# BMS_CellNode.net
KiCad netlist of a schematic drawn in Altium Designer
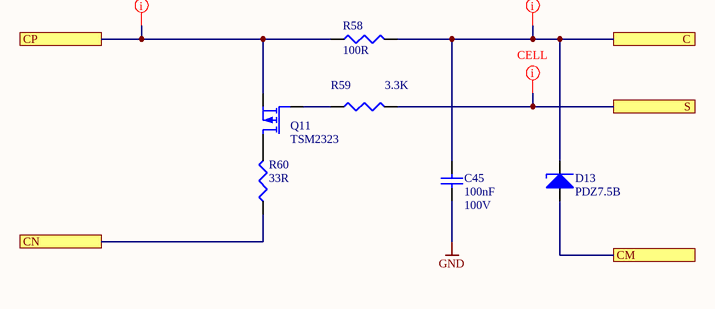
[diagram p0: BMS_CellNode.SchDoc]

(export (version "E")
  (design (tool "Eeschema 10.0.6"))
  (components
    (comp (ref "C45")
      (value "100nF")
      (footprint "VESC_BMS:C-0805")
      (description "Capacitor, 100nF, 100V, X7R")
      (fields (field (name "VOLTAGE RATING") "100V"))
      (libsource (lib "AR_Capacitors_Ceramic") (part "100nF/0805/CER/100V"))
    )
    (comp (ref "D13")
      (value "PDZ7.5B")
      (footprint "VESC_BMS:SOD-323")
      (description "Diode, Vrrm: 7.5V, If: 0.2A, Vf: 0.9V")
      (libsource (lib "AR_Diodes") (part "PDZ7.5B"))
    )
    (comp (ref "Q11")
      (value "TSM2323")
      (footprint "VESC_BMS:SOT-23")
      (description "Mosfet, P-channel, Vds:20V, Id:4.7A, Vgs-th:1V, Rds-on:0.039ohm")
      (libsource (lib "AR_Mosfets") (part "TSM2323"))
    )
    (comp (ref "R58")
      (value "100R")
      (footprint "VESC_BMS:0603")
      (description "Resistor, 100R, 1%, 0.063W, 50V, 200PPM, 0603")
      (libsource (lib "AR_Resistors_SMD") (part "100/0603/0063W/50V"))
    )
    (comp (ref "R59")
      (value "3.3K")
      (footprint "VESC_BMS:0603")
      (description "Resistor, 3.3K, 1%, 0.125W, 50V, 100PPM, 0603")
      (libsource (lib "AR_Resistors_SMD") (part "3.3K/0603/0125W/50V"))
    )
    (comp (ref "R60")
      (value "33R")
      (footprint "VESC_BMS:2512")
      (description "Resistor, 15R, 1%, 2W, 200V, 200PPM, 2512")
      (libsource (lib "AR_Resistors_SMD") (part "15/2512/2W/250V"))
    )
  )
  (nets
    (net (code "1") (name "/C") (class "Default")
      (node (ref "C45") (pin "2") (pinfunction "2_2") (pintype "passive"))
      (node (ref "D13") (pin "2") (pinfunction "2_2") (pintype "passive"))
      (node (ref "R58") (pin "2") (pinfunction "2_2") (pintype "passive"))
    )
    (net (code "2") (name "/CM") (class "Default")
      (node (ref "D13") (pin "1") (pinfunction "1_1") (pintype "passive"))
    )
    (net (code "3") (name "/CN") (class "Default")
      (node (ref "R60") (pin "1") (pinfunction "1_1") (pintype "passive"))
    )
    (net (code "4") (name "/CP") (class "Default")
      (node (ref "Q11") (pin "S") (pinfunction "S_S") (pintype "passive"))
      (node (ref "R58") (pin "1") (pinfunction "1_1") (pintype "passive"))
    )
    (net (code "5") (name "/S") (class "Default")
      (node (ref "R59") (pin "2") (pinfunction "2_2") (pintype "passive"))
    )
    (net (code "6") (name "GND") (class "Default")
      (node (ref "C45") (pin "1") (pinfunction "1_1") (pintype "passive"))
    )
    (net (code "7") (name "Net-(Q11-PadD)") (class "Default")
      (node (ref "Q11") (pin "D") (pinfunction "D_D") (pintype "passive"))
      (node (ref "R60") (pin "2") (pinfunction "2_2") (pintype "passive"))
    )
    (net (code "8") (name "Net-(Q11-PadG)") (class "Default")
      (node (ref "Q11") (pin "G") (pinfunction "G_G") (pintype "passive"))
      (node (ref "R59") (pin "1") (pinfunction "1_1") (pintype "passive"))
    )
  )
)
